# CH340G.net
KiCad netlist of a schematic drawn in Altium Designer
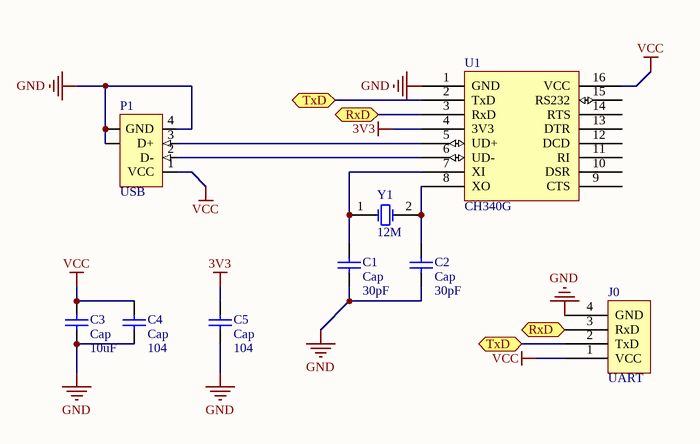
[diagram p0: CH340G.SchDoc]

(export (version "E")
  (design (tool "Eeschema 10.0.6"))
  (components
    (comp (ref "C1")
      (value "Cap")
      (footprint "C0805")
      (description "Capacitor")
      (fields (field (name "ALTIUM_VALUE") "30pF") (field (name "PUBLISHER") "Altium Limited"))
      (libsource (lib "Miscellaneous Devices") (part "Cap"))
    )
    (comp (ref "C2")
      (value "Cap")
      (footprint "C0805")
      (description "Capacitor")
      (fields (field (name "ALTIUM_VALUE") "30pF") (field (name "PUBLISHER") "Altium Limited"))
      (libsource (lib "Miscellaneous Devices") (part "Cap"))
    )
    (comp (ref "C3")
      (value "Cap")
      (footprint "C0805")
      (description "Capacitor")
      (fields (field (name "ALTIUM_VALUE") "10uF") (field (name "PUBLISHER") "Altium Limited"))
      (libsource (lib "Miscellaneous Devices") (part "Cap"))
    )
    (comp (ref "C4")
      (value "Cap")
      (footprint "C0805")
      (description "Capacitor")
      (fields (field (name "ALTIUM_VALUE") "104") (field (name "PUBLISHER") "Altium Limited"))
      (libsource (lib "Miscellaneous Devices") (part "Cap"))
    )
    (comp (ref "C5")
      (value "Cap")
      (footprint "C0805")
      (description "Capacitor")
      (fields (field (name "ALTIUM_VALUE") "104") (field (name "PUBLISHER") "Altium Limited"))
      (libsource (lib "Miscellaneous Devices") (part "Cap"))
    )
    (comp (ref "J0")
      (value "UART")
      (footprint "SIP4-2.54")
      (libsource (lib "PCB-Design-of-the-8051") (part "UART"))
    )
    (comp (ref "P1")
      (value "USB")
      (footprint "USB01")
      (description "USB 1.1, Right Angle, SMT, A Type, Plug, 4 Position, Natural")
      (fields (field (name "PUBLISHER") "Altium Limited"))
      (libsource (lib "jointbar") (part "USB"))
    )
    (comp (ref "U1")
      (value "CH340G")
      (footprint "SOP16")
      (libsource (lib "PCB-Design-of-the-8051") (part "CH340G"))
    )
    (comp (ref "Y1")
      (value "12M")
      (footprint "X-HC-49S")
      (description "Crystal Oscillator")
      (fields (field (name "PUBLISHER") "Altium Limited"))
      (libsource (lib "Miscellaneous Devices") (part "XTAL"))
    )
  )
  (nets
    (net (code "1") (name "/RxD") (class "Default")
      (node (ref "J0") (pin "3") (pinfunction "RxD_3") (pintype "passive"))
      (node (ref "U1") (pin "3") (pinfunction "RxD_3") (pintype "passive"))
    )
    (net (code "2") (name "/TxD") (class "Default")
      (node (ref "J0") (pin "2") (pinfunction "TxD_2") (pintype "passive"))
      (node (ref "U1") (pin "2") (pinfunction "TxD_2") (pintype "passive"))
    )
    (net (code "3") (name "3V3") (class "Default")
      (node (ref "C5") (pin "2") (pinfunction "2_2") (pintype "passive"))
      (node (ref "U1") (pin "4") (pinfunction "3V3_4") (pintype "passive"))
    )
    (net (code "4") (name "GND") (class "Default")
      (node (ref "C1") (pin "1") (pinfunction "1_1") (pintype "passive"))
      (node (ref "C2") (pin "1") (pinfunction "1_1") (pintype "passive"))
      (node (ref "C3") (pin "1") (pinfunction "1_1") (pintype "passive"))
      (node (ref "C4") (pin "1") (pinfunction "1_1") (pintype "passive"))
      (node (ref "C5") (pin "1") (pinfunction "1_1") (pintype "passive"))
      (node (ref "J0") (pin "4") (pinfunction "GND_4") (pintype "passive"))
      (node (ref "P1") (pin "4") (pinfunction "GND_4") (pintype "power_in"))
      (node (ref "P1") (pin "5") (pinfunction "SHLD_5") (pintype "passive"))
      (node (ref "P1") (pin "6") (pinfunction "SHLD_6") (pintype "passive"))
      (node (ref "U1") (pin "1") (pinfunction "GND_1") (pintype "power_in"))
    )
    (net (code "5") (name "Net-(P1-D+)") (class "Default")
      (node (ref "P1") (pin "3") (pinfunction "D+_3") (pintype "input"))
      (node (ref "U1") (pin "5") (pinfunction "UD+_5") (pintype "bidirectional"))
    )
    (net (code "6") (name "Net-(P1-D-)") (class "Default")
      (node (ref "P1") (pin "2") (pinfunction "D-_2") (pintype "input"))
      (node (ref "U1") (pin "6") (pinfunction "UD-_6") (pintype "bidirectional"))
    )
    (net (code "7") (name "Net-(U1-XI)") (class "Default")
      (node (ref "C1") (pin "2") (pinfunction "2_2") (pintype "passive"))
      (node (ref "U1") (pin "7") (pinfunction "XI_7") (pintype "passive"))
      (node (ref "Y1") (pin "1") (pinfunction "OSC1_1") (pintype "passive"))
    )
    (net (code "8") (name "Net-(U1-XO)") (class "Default")
      (node (ref "C2") (pin "2") (pinfunction "2_2") (pintype "passive"))
      (node (ref "U1") (pin "8") (pinfunction "XO_8") (pintype "passive"))
      (node (ref "Y1") (pin "2") (pinfunction "OSC2_2") (pintype "passive"))
    )
    (net (code "9") (name "VCC") (class "Default")
      (node (ref "C3") (pin "2") (pinfunction "2_2") (pintype "passive"))
      (node (ref "C4") (pin "2") (pinfunction "2_2") (pintype "passive"))
      (node (ref "J0") (pin "1") (pinfunction "VCC_1") (pintype "passive"))
      (node (ref "P1") (pin "1") (pinfunction "VCC_1") (pintype "power_in"))
      (node (ref "U1") (pin "16") (pinfunction "VCC_16") (pintype "power_in"))
    )
    (net (code "10") (name "unconnected-(U1-CTS-Pad9)") (class "Default")
      (node (ref "U1") (pin "9") (pinfunction "CTS_9") (pintype "passive"))
    )
    (net (code "11") (name "unconnected-(U1-DCD-Pad12)") (class "Default")
      (node (ref "U1") (pin "12") (pinfunction "DCD_12") (pintype "passive"))
    )
    (net (code "12") (name "unconnected-(U1-DSR-Pad10)") (class "Default")
      (node (ref "U1") (pin "10") (pinfunction "DSR_10") (pintype "passive"))
    )
    (net (code "13") (name "unconnected-(U1-DTR-Pad13)") (class "Default")
      (node (ref "U1") (pin "13") (pinfunction "DTR_13") (pintype "passive"))
    )
    (net (code "14") (name "unconnected-(U1-RI-Pad11)") (class "Default")
      (node (ref "U1") (pin "11") (pinfunction "RI_11") (pintype "passive"))
    )
    (net (code "15") (name "unconnected-(U1-RS232-Pad15)") (class "Default")
      (node (ref "U1") (pin "15") (pinfunction "RS232_15") (pintype "bidirectional"))
    )
    (net (code "16") (name "unconnected-(U1-RTS-Pad14)") (class "Default")
      (node (ref "U1") (pin "14") (pinfunction "RTS_14") (pintype "passive"))
    )
  )
)
